# V1_illuminationBoard_sch.net
KiCad netlist of a schematic drawn in Altium Designer
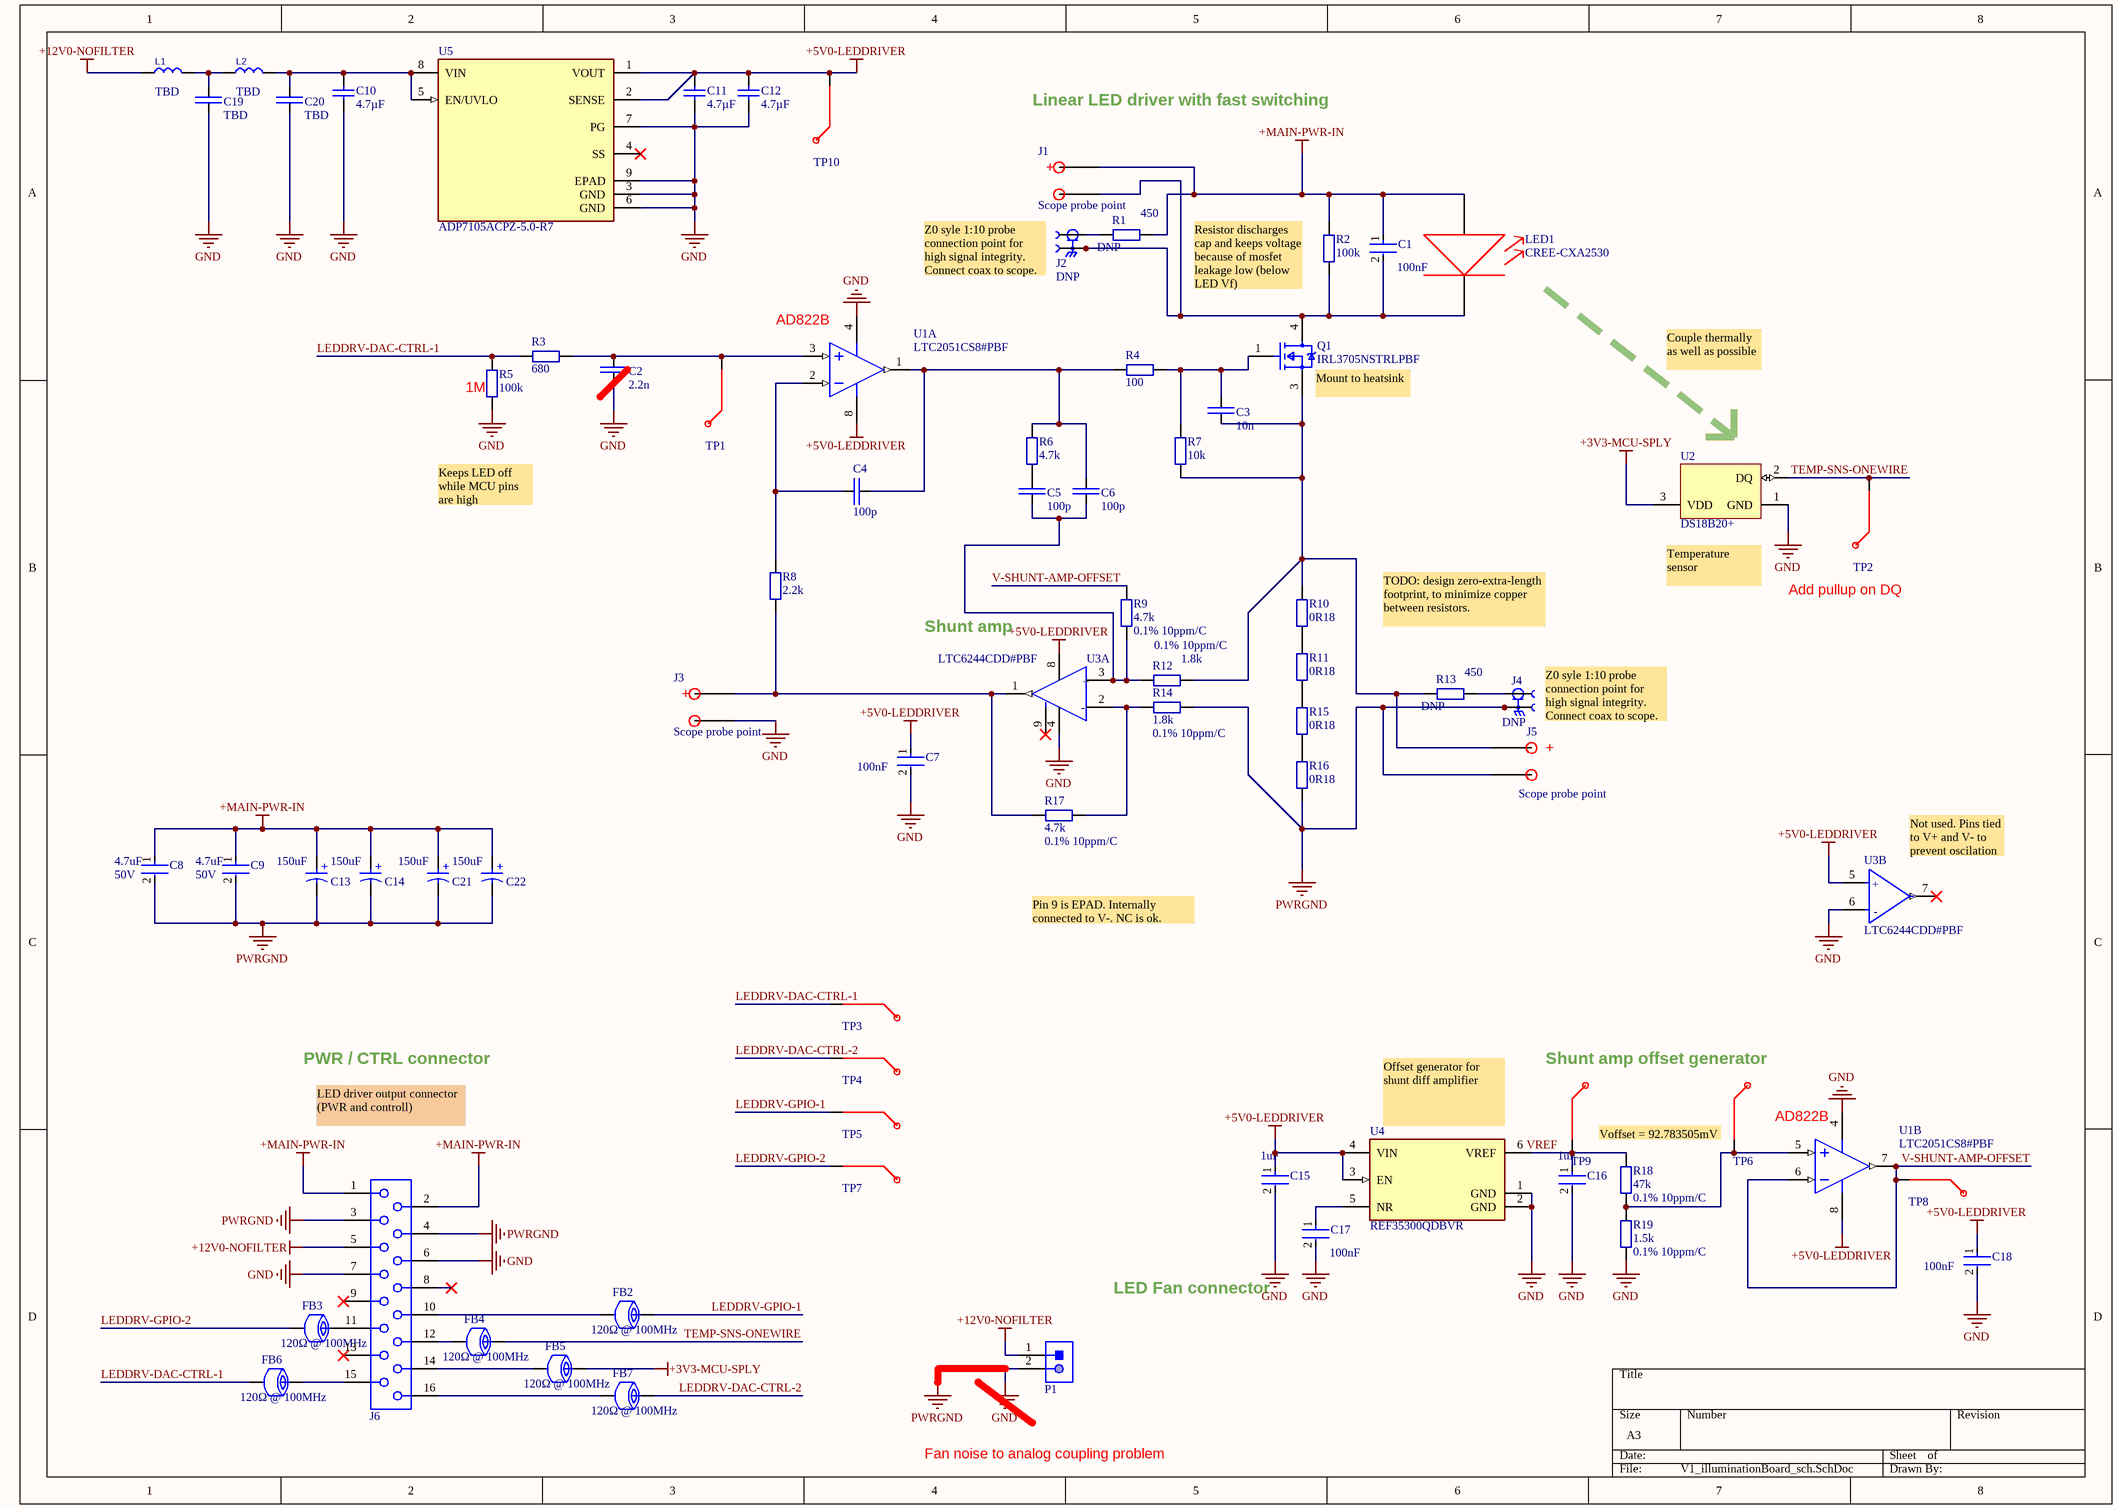
[diagram p0: V1_illuminationBoard_sch.SchDoc]

(export (version "E")
  (design (tool "Eeschema 10.0.6"))
  (components
    (comp (ref "C1")
      (value "885012206095")
      (footprint "FP-885012206095-IPC_B")
      (description "CAP CER 0.1UF 50V X7R 0603")
      (fields (field (name "TOLERANCE") "10%") (field (name "CAPACITANCE") "100nF"))
      (libsource (lib "Altium Content Vault") (part "11868f565c42a9108669ba33697ecf6"))
    )
    (comp (ref "C2")
      (value "2.2n")
      (footprint "Passives:FPR_0603_C_R0")
      (description "Capacitor - generic SMD")
      (fields (field (name "Comment") "PN_C0603_2n2"))
      (libsource (lib "Passives") (part "C"))
    )
    (comp (ref "C3")
      (value "10n")
      (footprint "Passives:FPR_0603_C_R0")
      (description "Capacitor - generic SMD")
      (fields (field (name "Comment") "PN_C0603_10n"))
      (libsource (lib "Passives") (part "C"))
    )
    (comp (ref "C4")
      (value "100p")
      (footprint "Passives:FPR_0603_C_R0")
      (description "Capacitor - generic SMD")
      (fields (field (name "Comment") "PN_C0603_100p"))
      (libsource (lib "Passives") (part "C"))
    )
    (comp (ref "C5")
      (value "100p")
      (footprint "Passives:FPR_0603_C_R0")
      (description "Capacitor - generic SMD")
      (fields (field (name "Comment") "PN_C0603_100p"))
      (libsource (lib "Passives") (part "C"))
    )
    (comp (ref "C6")
      (value "100p")
      (footprint "Passives:FPR_0603_C_R0")
      (description "Capacitor - generic SMD")
      (fields (field (name "Comment") "PN_C0603_100p"))
      (libsource (lib "Passives") (part "C"))
    )
    (comp (ref "C7")
      (value "885012206095")
      (footprint "FP-885012206095-IPC_B")
      (description "CAP CER 0.1UF 50V X7R 0603")
      (fields (field (name "TOLERANCE") "10%") (field (name "CAPACITANCE") "100nF"))
      (libsource (lib "Altium Content Vault") (part "11868f565c42a9108669ba33697ecf6"))
    )
    (comp (ref "C8")
      (value "885012208094")
      (footprint "FP-885012208094-IPC_B")
      (description "CAP CER 4.7UF 50V X7R 1206")
      (fields
        (field (name "VOLTAGE RATING (DC)") "50V")
        (field (name "CAPACITANCE") "4.7uF")
        (field (name "TOLERANCE") "10%")
      )
      (libsource (lib "Altium Content Vault") (part "11868f565c42a9108669ba33697ecf6"))
    )
    (comp (ref "C9")
      (value "885012208094")
      (footprint "FP-885012208094-IPC_B")
      (description "CAP CER 4.7UF 50V X7R 1206")
      (fields
        (field (name "VOLTAGE RATING (DC)") "50V")
        (field (name "CAPACITANCE") "4.7uF")
        (field (name "TOLERANCE") "10%")
      )
      (libsource (lib "Altium Content Vault") (part "11868f565c42a9108669ba33697ecf6"))
    )
    (comp (ref "C10")
      (value "885012107018")
      (footprint "WCAP-CSGP_0805_L2W1.25H1.25")
      (description "WCAP-CSGP Multilayer Ceramic Chip Capacitor, General Purpose, size 0805, X5R, 4.7µF, 25VDC")
      (fields (field (name "MANUFACTURER") "Wurth Elektronik") (field (name "CAPACITANCE") "4.7µF"))
      (libsource (lib "Altium_WCAP-CSGP (rev22f)") (part "885012107018"))
    )
    (comp (ref "C11")
      (value "885012107018")
      (footprint "WCAP-CSGP_0805_L2W1.25H1.25")
      (description "WCAP-CSGP Multilayer Ceramic Chip Capacitor, General Purpose, size 0805, X5R, 4.7µF, 25VDC")
      (fields (field (name "MANUFACTURER") "Wurth Elektronik") (field (name "CAPACITANCE") "4.7µF"))
      (libsource (lib "Altium_WCAP-CSGP (rev22f)") (part "885012107018"))
    )
    (comp (ref "C12")
      (value "885012107018")
      (footprint "WCAP-CSGP_0805_L2W1.25H1.25")
      (description "WCAP-CSGP Multilayer Ceramic Chip Capacitor, General Purpose, size 0805, X5R, 4.7µF, 25VDC")
      (fields (field (name "MANUFACTURER") "Wurth Elektronik") (field (name "CAPACITANCE") "4.7µF"))
      (libsource (lib "Altium_WCAP-CSGP (rev22f)") (part "885012107018"))
    )
    (comp (ref "C13")
      (value "865060657011")
      (footprint "WCAP-ASLL_D10H10.5")
      (description "WCAP-ASLL Aluminum Electrolytic Capacitor, V-Chip, D10 x H10.5mm, 150µF, 50V")
      (fields (field (name "MANUFACTURER") "Wurth Elektronik") (field (name "CAPACITANCE") "150uF"))
      (libsource (lib "Altium_WCAP-ASLL (rev22d)") (part "865060657011"))
    )
    (comp (ref "C14")
      (value "865060657011")
      (footprint "WCAP-ASLL_D10H10.5")
      (description "WCAP-ASLL Aluminum Electrolytic Capacitor, V-Chip, D10 x H10.5mm, 150µF, 50V")
      (fields (field (name "MANUFACTURER") "Wurth Elektronik") (field (name "CAPACITANCE") "150uF"))
      (libsource (lib "Altium_WCAP-ASLL (rev22d)") (part "865060657011"))
    )
    (comp (ref "C15")
      (value "885012207078")
      (footprint "FP-885012207078-IPC_B")
      (description "CAP CER 1UF 25V X7R 0805")
      (fields (field (name "CAPACITANCE") "1uF") (field (name "TOLERANCE") "10%"))
      (libsource (lib "Altium Content Vault") (part "b4654b650e69147ec39a6b967a45e02"))
    )
    (comp (ref "C16")
      (value "885012207078")
      (footprint "FP-885012207078-IPC_B")
      (description "CAP CER 1UF 25V X7R 0805")
      (fields (field (name "CAPACITANCE") "1uF") (field (name "TOLERANCE") "10%"))
      (libsource (lib "Altium Content Vault") (part "b4654b650e69147ec39a6b967a45e02"))
    )
    (comp (ref "C17")
      (value "885012206095")
      (footprint "FP-885012206095-IPC_B")
      (description "CAP CER 0.1UF 50V X7R 0603")
      (fields (field (name "TOLERANCE") "10%") (field (name "CAPACITANCE") "100nF"))
      (libsource (lib "Altium Content Vault") (part "11868f565c42a9108669ba33697ecf6"))
    )
    (comp (ref "C18")
      (value "885012206095")
      (footprint "FP-885012206095-IPC_B")
      (description "CAP CER 0.1UF 50V X7R 0603")
      (fields (field (name "TOLERANCE") "10%") (field (name "CAPACITANCE") "100nF"))
      (libsource (lib "Altium Content Vault") (part "11868f565c42a9108669ba33697ecf6"))
    )
    (comp (ref "C19")
      (value "TBD")
      (footprint "Passives:FPR_0603_C_R0")
      (description "Capacitor - generic SMD")
      (fields (field (name "Comment") "PN_C0603_TBD"))
      (libsource (lib "Passives") (part "C"))
    )
    (comp (ref "C20")
      (value "TBD")
      (footprint "Passives:FPR_0603_C_R0")
      (description "Capacitor - generic SMD")
      (fields (field (name "Comment") "PN_C0603_TBD"))
      (libsource (lib "Passives") (part "C"))
    )
    (comp (ref "C21")
      (value "865060657011")
      (footprint "WCAP-ASLL_D10H10.5")
      (description "WCAP-ASLL Aluminum Electrolytic Capacitor, V-Chip, D10 x H10.5mm, 150µF, 50V")
      (fields (field (name "MANUFACTURER") "Wurth Elektronik") (field (name "CAPACITANCE") "150uF"))
      (libsource (lib "Altium_WCAP-ASLL (rev22d)") (part "865060657011"))
    )
    (comp (ref "C22")
      (value "865060657011")
      (footprint "WCAP-ASLL_D10H10.5")
      (description "WCAP-ASLL Aluminum Electrolytic Capacitor, V-Chip, D10 x H10.5mm, 150µF, 50V")
      (fields (field (name "MANUFACTURER") "Wurth Elektronik") (field (name "CAPACITANCE") "150uF"))
      (libsource (lib "Altium_WCAP-ASLL (rev22d)") (part "865060657011"))
    )
    (comp (ref "FB2")
      (value "120Ω @ 100MHz")
      (footprint "SMD_0805")
      (description "Ferrite Bead, 0805 [2012 Metric], 120 ohm, 800 mA, BLM21A Series, 0.15 ohm, ± 25%")
      (fields (field (name "MANUFACTURER") "Murata"))
      (libsource (lib "DAQ_REV_B") (part "BLM21AG121SN1D"))
    )
    (comp (ref "FB3")
      (value "120Ω @ 100MHz")
      (footprint "SMD_0805")
      (description "Ferrite Bead, 0805 [2012 Metric], 120 ohm, 800 mA, BLM21A Series, 0.15 ohm, ± 25%")
      (fields (field (name "MANUFACTURER") "Murata"))
      (libsource (lib "DAQ_REV_B") (part "BLM21AG121SN1D"))
    )
    (comp (ref "FB4")
      (value "120Ω @ 100MHz")
      (footprint "SMD_0805")
      (description "Ferrite Bead, 0805 [2012 Metric], 120 ohm, 800 mA, BLM21A Series, 0.15 ohm, ± 25%")
      (fields (field (name "MANUFACTURER") "Murata"))
      (libsource (lib "DAQ_REV_B") (part "BLM21AG121SN1D"))
    )
    (comp (ref "FB5")
      (value "120Ω @ 100MHz")
      (footprint "SMD_0805")
      (description "Ferrite Bead, 0805 [2012 Metric], 120 ohm, 800 mA, BLM21A Series, 0.15 ohm, ± 25%")
      (fields (field (name "MANUFACTURER") "Murata"))
      (libsource (lib "DAQ_REV_B") (part "BLM21AG121SN1D"))
    )
    (comp (ref "FB6")
      (value "120Ω @ 100MHz")
      (footprint "SMD_0805")
      (description "Ferrite Bead, 0805 [2012 Metric], 120 ohm, 800 mA, BLM21A Series, 0.15 ohm, ± 25%")
      (fields (field (name "MANUFACTURER") "Murata"))
      (libsource (lib "DAQ_REV_B") (part "BLM21AG121SN1D"))
    )
    (comp (ref "FB7")
      (value "120Ω @ 100MHz")
      (footprint "SMD_0805")
      (description "Ferrite Bead, 0805 [2012 Metric], 120 ohm, 800 mA, BLM21A Series, 0.15 ohm, ± 25%")
      (fields (field (name "MANUFACTURER") "Murata"))
      (libsource (lib "DAQ_REV_B") (part "BLM21AG121SN1D"))
    )
    (comp (ref "J1")
      (value "Scope probe point")
      (footprint "scope with ground spring probe point")
      (libsource (lib "planinsekLib_sch") (part "Scope probe point"))
    )
    (comp (ref "J2")
      (value "CONUFL001-SMD-T")
      (footprint "LINX_CONUFL001-SMD-T")
      (description "U.FL (UMCC) Connector Jack, Male Pin 50Ohm Surface Mount Solder")
      (fields (field (name "MF") "Linx") (field (name "DNP") "DNP"))
      (libsource (lib "") (part "CONUFL001-SMD-T_1"))
    )
    (comp (ref "J3")
      (value "Scope probe point")
      (footprint "scope with ground spring probe point")
      (libsource (lib "planinsekLib_sch") (part "Scope probe point"))
    )
    (comp (ref "J4")
      (value "CONUFL001-SMD-T")
      (footprint "LINX_CONUFL001-SMD-T")
      (description "U.FL (UMCC) Connector Jack, Male Pin 50Ohm Surface Mount Solder")
      (fields (field (name "MF") "Linx") (field (name "DNP") "DNP"))
      (libsource (lib "CONUFL001-SMD-T") (part "CONUFL001-SMD-T"))
    )
    (comp (ref "J5")
      (value "Scope probe point")
      (footprint "scope with ground spring probe point")
      (libsource (lib "") (part "Scope probe point_1"))
    )
    (comp (ref "J6")
      (value "690368191672")
      (footprint "690368191672")
      (description "WR-MM Mini Module Connector, Female, THT, with Latch & Polarization, Angled, pitch 2.54mm, 16p")
      (fields (field (name "MANUFACTURER") "Wurth Elektronik"))
      (libsource (lib "Altium_WR-MM (rev22a)") (part "690368191672"))
    )
    (comp (ref "L1")
      (value "TBD")
      (footprint "FPR_1216_R_R0")
      (description "Inductor - generic SMD")
      (fields (field (name "Comment") "L-TBD"))
      (libsource (lib "Passives") (part "L"))
    )
    (comp (ref "L2")
      (value "TBD")
      (footprint "FPR_1216_R_R0")
      (description "Inductor - generic SMD")
      (fields (field (name "Comment") "L-TBD"))
      (libsource (lib "Passives") (part "L"))
    )
    (comp (ref "LED1")
      (value "CREE-CXA2530")
      (footprint "CXA2530-SolderMount")
      (description "High power LED")
      (libsource (lib "planinsekLib_sch") (part "CREE CXA2530"))
    )
    (comp (ref "P1")
      (value "61300211121")
      (footprint "61300211121")
      (description "THT Vertical Pin Header WR-PHD, Pitch 2.54 mm, Single Row, 2 pins")
      (fields (field (name "MANUFACTURER") "Wurth Elektronik") (field (name "PUBLISHER") "WurthElektronik"))
      (libsource (lib "Altium Content Vault") (part "WE-CN-1P-M-R2"))
    )
    (comp (ref "Q1")
      (value "IRL3705NSTRLPBF")
      (footprint "FP-PG-TO263-3-MFG")
      (description "MOSFET N-CH 55V 89A D2PAK")
      (libsource (lib "Altium Content Vault") (part "2f21c11e83d30f418bb422e5a3b3d11"))
    )
    (comp (ref "R1")
      (value "450")
      (footprint "Passives:FPR_0603_R_R0")
      (description "Resistor - generic SMD")
      (fields (field (name "DNP") "DNP") (field (name "Comment") "PN_R0603_450R"))
      (libsource (lib "Passives") (part "R"))
    )
    (comp (ref "R2")
      (value "100k")
      (footprint "Passives:FPR_0603_R_R0")
      (description "Resistor - generic SMD")
      (fields (field (name "Comment") "PN_R0603_100k"))
      (libsource (lib "Passives") (part "R"))
    )
    (comp (ref "R3")
      (value "680")
      (footprint "Passives:FPR_0603_R_R0")
      (description "Resistor - generic SMD")
      (fields (field (name "Comment") "PN_R0603_680R"))
      (libsource (lib "Passives") (part "R"))
    )
    (comp (ref "R4")
      (value "100")
      (footprint "Passives:FPR_0603_R_R0")
      (description "Resistor - generic SMD")
      (fields (field (name "Comment") "PN_R0603_100R"))
      (libsource (lib "Passives") (part "R"))
    )
    (comp (ref "R5")
      (value "100k")
      (footprint "Passives:FPR_0603_R_R0")
      (description "Resistor - generic SMD")
      (fields (field (name "Comment") "PN_R0603_100k"))
      (libsource (lib "Passives") (part "R"))
    )
    (comp (ref "R6")
      (value "4.7k")
      (footprint "Passives:FPR_0603_R_R0")
      (description "Resistor - generic SMD")
      (fields (field (name "Comment") "PN_R0603_4k7"))
      (libsource (lib "Passives") (part "R"))
    )
    (comp (ref "R7")
      (value "10k")
      (footprint "Passives:FPR_0603_R_R0")
      (description "Resistor - generic SMD")
      (fields (field (name "Comment") "PN_R0603_10k"))
      (libsource (lib "Passives") (part "R"))
    )
    (comp (ref "R8")
      (value "2.2k")
      (footprint "Passives:FPR_0603_R_R0")
      (description "Resistor - generic SMD")
      (fields (field (name "Comment") "PN_R0603_2k2"))
      (libsource (lib "Passives") (part "R"))
    )
    (comp (ref "R9")
      (value "4.7k")
      (footprint "Passives:FPR_0603_R_R0")
      (description "Resistor - generic SMD")
      (fields (field (name "TOLERANCE") "0.1% 10ppm/C") (field (name "Comment") "PN_R0603_4k7_0%1_10ppm"))
      (libsource (lib "Passives") (part "R"))
    )
    (comp (ref "R10")
      (value "0R18")
      (footprint "FPR_CRF2512_R0-endToEnd")
      (description "Resistor - generic SMD")
      (fields (field (name "Comment") "TLRP3A30CR180FTE"))
      (libsource (lib "Passives") (part "R"))
    )
    (comp (ref "R11")
      (value "0R18")
      (footprint "FPR_CRF2512_R0-endToEnd")
      (description "Resistor - generic SMD")
      (fields (field (name "Comment") "TLRP3A30CR180FTE"))
      (libsource (lib "Passives") (part "R"))
    )
    (comp (ref "R12")
      (value "1.8k")
      (footprint "Passives:FPR_0603_R_R0")
      (description "Resistor - generic SMD")
      (fields (field (name "TOLERANCE") "0.1% 10ppm/C") (field (name "Comment") "PN_R0603_1k8_0%1_10ppm"))
      (libsource (lib "Passives") (part "R"))
    )
    (comp (ref "R13")
      (value "450")
      (footprint "Passives:FPR_0603_R_R0")
      (description "Resistor - generic SMD")
      (fields (field (name "DNP") "DNP") (field (name "Comment") "PN_R0603_450R"))
      (libsource (lib "Passives") (part "R"))
    )
    (comp (ref "R14")
      (value "1.8k")
      (footprint "Passives:FPR_0603_R_R0")
      (description "Resistor - generic SMD")
      (fields (field (name "TOLERANCE") "0.1% 10ppm/C") (field (name "Comment") "PN_R0603_1k8_0%1_10ppm"))
      (libsource (lib "Passives") (part "R"))
    )
    (comp (ref "R15")
      (value "0R18")
      (footprint "FPR_CRF2512_R0-endToEnd")
      (description "Resistor - generic SMD")
      (fields (field (name "Comment") "TLRP3A30CR180FTE"))
      (libsource (lib "Passives") (part "R"))
    )
    (comp (ref "R16")
      (value "0R18")
      (footprint "FPR_CRF2512_R0-endToEnd")
      (description "Resistor - generic SMD")
      (fields (field (name "Comment") "TLRP3A30CR180FTE"))
      (libsource (lib "Passives") (part "R"))
    )
    (comp (ref "R17")
      (value "4.7k")
      (footprint "Passives:FPR_0603_R_R0")
      (description "Resistor - generic SMD")
      (fields (field (name "TOLERANCE") "0.1% 10ppm/C") (field (name "Comment") "PN_R0603_4k7_0%1_10ppm"))
      (libsource (lib "Passives") (part "R"))
    )
    (comp (ref "R18")
      (value "47k")
      (footprint "Passives:FPR_0603_R_R0")
      (description "Resistor - generic SMD")
      (fields (field (name "TOLERANCE") "0.1% 10ppm/C") (field (name "Comment") "PN_R0603_47k_0%1_10ppm"))
      (libsource (lib "Passives") (part "R"))
    )
    (comp (ref "R19")
      (value "1.5k")
      (footprint "Passives:FPR_0603_R_R0")
      (description "Resistor - generic SMD")
      (fields (field (name "TOLERANCE") "0.1% 10ppm/C") (field (name "Comment") "PN_R0603_1k5_0%1_10ppm"))
      (libsource (lib "Passives") (part "R"))
    )
    (comp (ref "TP1")
      (value "Test Point")
      (footprint "Test Point 1.5mm SMD")
      (libsource (lib "planinsekLib_sch") (part "Test Point"))
    )
    (comp (ref "TP2")
      (value "Test Point")
      (footprint "Test Point 1.5mm SMD")
      (libsource (lib "planinsekLib_sch") (part "Test Point"))
    )
    (comp (ref "TP3")
      (value "Test Point")
      (footprint "Test Point 1.5mm SMD")
      (libsource (lib "planinsekLib_sch") (part "Test Point"))
    )
    (comp (ref "TP4")
      (value "Test Point")
      (footprint "Test Point 1.5mm SMD")
      (libsource (lib "planinsekLib_sch") (part "Test Point"))
    )
    (comp (ref "TP5")
      (value "Test Point")
      (footprint "Test Point 1.5mm SMD")
      (libsource (lib "planinsekLib_sch") (part "Test Point"))
    )
    (comp (ref "TP6")
      (value "Test Point")
      (footprint "Test Point 1.5mm SMD")
      (libsource (lib "planinsekLib_sch") (part "Test Point"))
    )
    (comp (ref "TP7")
      (value "Test Point")
      (footprint "Test Point 1.5mm SMD")
      (libsource (lib "planinsekLib_sch") (part "Test Point"))
    )
    (comp (ref "TP8")
      (value "Test Point")
      (footprint "Test Point 1.5mm SMD")
      (libsource (lib "planinsekLib_sch") (part "Test Point"))
    )
    (comp (ref "TP9")
      (value "Test Point")
      (footprint "Test Point 1.5mm SMD")
      (libsource (lib "planinsekLib_sch") (part "Test Point"))
    )
    (comp (ref "TP10")
      (value "Test Point")
      (footprint "Test Point 1.5mm SMD")
      (libsource (lib "planinsekLib_sch") (part "Test Point"))
    )
    (comp (ref "U1")
      (value "LTC2051CS8#PBF")
      (footprint "LT-S8-8_N")
      (fields
        (field (name "MANUFACTURER") "Linear Technology")
        (field (name "LINEAR TECHNOLOGY PART NUMBER") "LTC2051")
      )
      (libsource (lib "Altium Content Vault") (part "LT-LT1364-LT18XX-8"))
    )
    (comp (ref "U2")
      (value "DS18B20+")
      (footprint "to-92 horiyontal boardhole")
      (libsource (lib "ds18b20") (part "CMP-0253-00003-1"))
    )
    (comp (ref "U3")
      (value "LTC6244CDD#PBF")
      (footprint "FP-DD-8-05-08-1698-IPC_A")
      (description "IC CMOS 2 CIRCUIT 8DFN")
      (libsource (lib "Altium Content Vault") (part "2f377bccdb376714fb973d3e24d9851"))
    )
    (comp (ref "U4")
      (value "REF35300QDBVR")
      (footprint "FP-DBV0006A-MFG")
      (description "650-NA QUIESCENT CURRENT, 12-PPM, 3V out")
      (libsource (lib "Altium Content Vault") (part "73067d3f248247d8aed0d86424b3493"))
    )
    (comp (ref "U5")
      (value "ADP7105ACPZ-5.0-R7")
      (footprint "FP-CP-8-5-IPC_C")
      (description "IC REG LINEAR 5V 500MA 8LFCSP")
      (libsource (lib "Altium Content Vault") (part "3afc8f7b7a475b796d1e7b3a9bf20b9"))
    )
  )
  (nets
    (net (code "1") (name "+3V3-MCU-SPLY") (class "Default")
      (node (ref "FB5") (pin "1") (pintype "passive"))
      (node (ref "U2") (pin "3") (pinfunction "VDD_3") (pintype "power_in"))
    )
    (net (code "2") (name "+5V0-LEDDRIVER") (class "Default")
      (node (ref "C11") (pin "2") (pinfunction "2_2") (pintype "passive"))
      (node (ref "C12") (pin "2") (pinfunction "2_2") (pintype "passive"))
      (node (ref "C15") (pin "1") (pinfunction "1_1") (pintype "passive"))
      (node (ref "C18") (pin "1") (pinfunction "1_1") (pintype "passive"))
      (node (ref "C7") (pin "1") (pinfunction "1_1") (pintype "passive"))
      (node (ref "TP10") (pin "1") (pintype "passive"))
      (node (ref "U1") (pin "8") (pinfunction "V+_8") (pintype "power_in"))
      (node (ref "U3") (pin "5") (pinfunction "+IN_B_5") (pintype "tri_state"))
      (node (ref "U3") (pin "8") (pinfunction "V+_8") (pintype "power_in"))
      (node (ref "U4") (pin "3") (pinfunction "EN_3") (pintype "input"))
      (node (ref "U4") (pin "4") (pinfunction "VIN_4") (pintype "power_in"))
      (node (ref "U5") (pin "1") (pinfunction "VOUT_1") (pintype "power_in"))
      (node (ref "U5") (pin "2") (pinfunction "SENSE_2") (pintype "power_in"))
    )
    (net (code "3") (name "+12V0-NOFILTER") (class "Default")
      (node (ref "J6") (pin "5") (pinfunction "5_5") (pintype "passive"))
      (node (ref "L1") (pin "1") (pintype "passive"))
      (node (ref "P1") (pin "1") (pinfunction "1_1") (pintype "passive"))
    )
    (net (code "4") (name "+MAIN-PWR-IN") (class "Default")
      (node (ref "C1") (pin "1") (pinfunction "1_1") (pintype "passive"))
      (node (ref "C13") (pin "1") (pinfunction "P_1") (pintype "passive"))
      (node (ref "C14") (pin "1") (pinfunction "P_1") (pintype "passive"))
      (node (ref "C21") (pin "1") (pinfunction "P_1") (pintype "passive"))
      (node (ref "C22") (pin "1") (pinfunction "P_1") (pintype "passive"))
      (node (ref "C8") (pin "1") (pinfunction "1_1") (pintype "passive"))
      (node (ref "C9") (pin "1") (pinfunction "1_1") (pintype "passive"))
      (node (ref "J1") (pin "POS") (pinfunction "POS_POS") (pintype "passive"))
      (node (ref "J6") (pin "1") (pinfunction "1_1") (pintype "passive"))
      (node (ref "J6") (pin "2") (pinfunction "2_2") (pintype "passive"))
      (node (ref "LED1") (pin "POS") (pinfunction "POS_POS") (pintype "passive"))
      (node (ref "R1") (pin "2") (pinfunction "2_2") (pintype "passive"))
      (node (ref "R2") (pin "2") (pinfunction "2_2") (pintype "passive"))
    )
    (net (code "5") (name "/LEDDRV-DAC-CTRL-1") (class "Default")
      (node (ref "FB6") (pin "2") (pintype "passive"))
      (node (ref "R3") (pin "2") (pinfunction "2_2") (pintype "passive"))
      (node (ref "R5") (pin "2") (pinfunction "2_2") (pintype "passive"))
      (node (ref "TP3") (pin "1") (pintype "passive"))
    )
    (net (code "6") (name "/LEDDRV-DAC-CTRL-2") (class "Default")
      (node (ref "FB7") (pin "1") (pintype "passive"))
      (node (ref "TP4") (pin "1") (pintype "passive"))
    )
    (net (code "7") (name "/LEDDRV-GPIO-1") (class "Default")
      (node (ref "FB2") (pin "1") (pintype "passive"))
      (node (ref "TP5") (pin "1") (pintype "passive"))
    )
    (net (code "8") (name "/LEDDRV-GPIO-2") (class "Default")
      (node (ref "FB3") (pin "2") (pintype "passive"))
      (node (ref "TP7") (pin "1") (pintype "passive"))
    )
    (net (code "9") (name "/TEMP-SNS-ONEWIRE") (class "Default")
      (node (ref "FB4") (pin "1") (pintype "passive"))
      (node (ref "TP2") (pin "1") (pintype "passive"))
      (node (ref "U2") (pin "2") (pinfunction "DQ_2") (pintype "bidirectional"))
    )
    (net (code "10") (name "/V-SHUNT-AMP-OFFSET") (class "Default")
      (node (ref "R9") (pin "2") (pinfunction "2_2") (pintype "passive"))
      (node (ref "TP8") (pin "1") (pintype "passive"))
      (node (ref "U1") (pin "6") (pinfunction "-IN_B_6") (pintype "input"))
      (node (ref "U1") (pin "7") (pinfunction "OUT_B_7") (pintype "output"))
    )
    (net (code "11") (name "/VREF") (class "Default")
      (node (ref "C16") (pin "1") (pinfunction "1_1") (pintype "passive"))
      (node (ref "R18") (pin "1") (pinfunction "1_1") (pintype "passive"))
      (node (ref "TP9") (pin "1") (pintype "passive"))
      (node (ref "U4") (pin "6") (pinfunction "VREF_6") (pintype "passive"))
    )
    (net (code "12") (name "GND") (class "Default")
      (node (ref "C10") (pin "1") (pinfunction "1_1") (pintype "passive"))
      (node (ref "C11") (pin "1") (pinfunction "1_1") (pintype "passive"))
      (node (ref "C12") (pin "1") (pinfunction "1_1") (pintype "passive"))
      (node (ref "C15") (pin "2") (pinfunction "2_2") (pintype "passive"))
      (node (ref "C16") (pin "2") (pinfunction "2_2") (pintype "passive"))
      (node (ref "C17") (pin "2") (pinfunction "2_2") (pintype "passive"))
      (node (ref "C18") (pin "2") (pinfunction "2_2") (pintype "passive"))
      (node (ref "C19") (pin "1") (pinfunction "1_1") (pintype "passive"))
      (node (ref "C2") (pin "2") (pinfunction "2_2") (pintype "passive"))
      (node (ref "C20") (pin "1") (pinfunction "1_1") (pintype "passive"))
      (node (ref "C7") (pin "2") (pinfunction "2_2") (pintype "passive"))
      (node (ref "J3") (pin "NEG") (pinfunction "NEG_NEG") (pintype "passive"))
      (node (ref "J6") (pin "6") (pinfunction "6_6") (pintype "passive"))
      (node (ref "J6") (pin "7") (pinfunction "7_7") (pintype "passive"))
      (node (ref "P1") (pin "2") (pinfunction "2_2") (pintype "passive"))
      (node (ref "R19") (pin "2") (pinfunction "2_2") (pintype "passive"))
      (node (ref "R5") (pin "1") (pinfunction "1_1") (pintype "passive"))
      (node (ref "U1") (pin "4") (pinfunction "V-_4") (pintype "power_in"))
      (node (ref "U2") (pin "1") (pinfunction "GND_1") (pintype "power_in"))
      (node (ref "U3") (pin "4") (pinfunction "V-_4") (pintype "power_in"))
      (node (ref "U3") (pin "6") (pinfunction "-IN_B_6") (pintype "tri_state"))
      (node (ref "U4") (pin "1") (pinfunction "GND_1") (pintype "power_in"))
      (node (ref "U4") (pin "2") (pinfunction "GND_2") (pintype "power_in"))
      (node (ref "U5") (pin "3") (pinfunction "GND_3") (pintype "power_in"))
      (node (ref "U5") (pin "6") (pinfunction "GND_6") (pintype "power_in"))
      (node (ref "U5") (pin "7") (pinfunction "PG_7") (pintype "open_collector"))
      (node (ref "U5") (pin "9") (pinfunction "EPAD_9") (pintype "power_in"))
    )
    (net (code "13") (name "Net-(C5-Pad1)") (class "Default")
      (node (ref "C5") (pin "1") (pinfunction "1_1") (pintype "passive"))
      (node (ref "R6") (pin "1") (pinfunction "1_1") (pintype "passive"))
    )
    (net (code "14") (name "Net-(C19-Pad2)") (class "Default")
      (node (ref "C19") (pin "2") (pinfunction "2_2") (pintype "passive"))
      (node (ref "L1") (pin "2") (pintype "passive"))
      (node (ref "L2") (pin "1") (pintype "passive"))
    )
    (net (code "15") (name "Net-(FB2-Pad2)") (class "Default")
      (node (ref "FB2") (pin "2") (pintype "passive"))
      (node (ref "J6") (pin "10") (pinfunction "10_10") (pintype "passive"))
    )
    (net (code "16") (name "Net-(FB3-Pad1)") (class "Default")
      (node (ref "FB3") (pin "1") (pintype "passive"))
      (node (ref "J6") (pin "11") (pinfunction "11_11") (pintype "passive"))
    )
    (net (code "17") (name "Net-(FB4-Pad2)") (class "Default")
      (node (ref "FB4") (pin "2") (pintype "passive"))
      (node (ref "J6") (pin "12") (pinfunction "12_12") (pintype "passive"))
    )
    (net (code "18") (name "Net-(FB5-Pad2)") (class "Default")
      (node (ref "FB5") (pin "2") (pintype "passive"))
      (node (ref "J6") (pin "14") (pinfunction "14_14") (pintype "passive"))
    )
    (net (code "19") (name "Net-(FB6-Pad1)") (class "Default")
      (node (ref "FB6") (pin "1") (pintype "passive"))
      (node (ref "J6") (pin "15") (pinfunction "15_15") (pintype "passive"))
    )
    (net (code "20") (name "Net-(FB7-Pad2)") (class "Default")
      (node (ref "FB7") (pin "2") (pintype "passive"))
      (node (ref "J6") (pin "16") (pinfunction "16_16") (pintype "passive"))
    )
    (net (code "21") (name "Net-(J2-Pad1)") (class "Default")
      (node (ref "J2") (pin "1") (pinfunction "1_1") (pintype "passive"))
      (node (ref "R1") (pin "1") (pinfunction "1_1") (pintype "passive"))
    )
    (net (code "22") (name "Net-(J4-Pad1)") (class "Default")
      (node (ref "J4") (pin "1") (pinfunction "1_1") (pintype "passive"))
      (node (ref "R13") (pin "1") (pinfunction "1_1") (pintype "passive"))
    )
    (net (code "23") (name "Net-(Q1-DRAIN)") (class "Default")
      (node (ref "C1") (pin "2") (pinfunction "2_2") (pintype "passive"))
      (node (ref "J1") (pin "NEG") (pinfunction "NEG_NEG") (pintype "passive"))
      (node (ref "J2") (pin "2") (pinfunction "2_2") (pintype "passive"))
      (node (ref "J2") (pin "3") (pinfunction "2_3") (pintype "passive"))
      (node (ref "LED1") (pin "NEG") (pinfunction "NEG_NEG") (pintype "passive"))
      (node (ref "Q1") (pin "4") (pinfunction "DRAIN_4") (pintype "passive"))
      (node (ref "R2") (pin "1") (pinfunction "1_1") (pintype "passive"))
    )
    (net (code "24") (name "Net-(Q1-GATE)") (class "Default")
      (node (ref "C3") (pin "2") (pinfunction "2_2") (pintype "passive"))
      (node (ref "Q1") (pin "1") (pinfunction "GATE_1") (pintype "passive"))
      (node (ref "R4") (pin "2") (pinfunction "2_2") (pintype "passive"))
      (node (ref "R7") (pin "2") (pinfunction "2_2") (pintype "passive"))
    )
    (net (code "25") (name "Net-(Q1-SOURCE)") (class "Default")
      (node (ref "C3") (pin "1") (pinfunction "1_1") (pintype "passive"))
      (node (ref "J5") (pin "POS") (pinfunction "POS_POS") (pintype "passive"))
      (node (ref "Q1") (pin "3") (pinfunction "SOURCE_3") (pintype "passive"))
      (node (ref "R10") (pin "2") (pinfunction "2_2") (pintype "passive"))
      (node (ref "R12") (pin "1") (pinfunction "1_1") (pintype "passive"))
      (node (ref "R13") (pin "2") (pinfunction "2_2") (pintype "passive"))
      (node (ref "R7") (pin "1") (pinfunction "1_1") (pintype "passive"))
    )
    (net (code "26") (name "Net-(R10-Pad1)") (class "Default")
      (node (ref "R10") (pin "1") (pinfunction "1_1") (pintype "passive"))
      (node (ref "R11") (pin "2") (pinfunction "2_2") (pintype "passive"))
    )
    (net (code "27") (name "Net-(R11-Pad1)") (class "Default")
      (node (ref "R11") (pin "1") (pinfunction "1_1") (pintype "passive"))
      (node (ref "R15") (pin "2") (pinfunction "2_2") (pintype "passive"))
    )
    (net (code "28") (name "Net-(R15-Pad1)") (class "Default")
      (node (ref "R15") (pin "1") (pinfunction "1_1") (pintype "passive"))
      (node (ref "R16") (pin "2") (pinfunction "2_2") (pintype "passive"))
    )
    (net (code "29") (name "Net-(U1A-+IN_A)") (class "Default")
      (node (ref "C2") (pin "1") (pinfunction "1_1") (pintype "passive"))
      (node (ref "R3") (pin "1") (pinfunction "1_1") (pintype "passive"))
      (node (ref "TP1") (pin "1") (pintype "passive"))
      (node (ref "U1") (pin "3") (pinfunction "+IN_A_3") (pintype "input"))
    )
    (net (code "30") (name "Net-(U1A--IN_A)") (class "Default")
      (node (ref "C4") (pin "2") (pinfunction "2_2") (pintype "passive"))
      (node (ref "R8") (pin "2") (pinfunction "2_2") (pintype "passive"))
      (node (ref "U1") (pin "2") (pinfunction "-IN_A_2") (pintype "input"))
    )
    (net (code "31") (name "Net-(U1A-OUT_A)") (class "Default")
      (node (ref "C4") (pin "1") (pinfunction "1_1") (pintype "passive"))
      (node (ref "C6") (pin "1") (pinfunction "1_1") (pintype "passive"))
      (node (ref "R4") (pin "1") (pinfunction "1_1") (pintype "passive"))
      (node (ref "R6") (pin "2") (pinfunction "2_2") (pintype "passive"))
      (node (ref "U1") (pin "1") (pinfunction "OUT_A_1") (pintype "output"))
    )
    (net (code "32") (name "Net-(U1B-+IN_B)") (class "Default")
      (node (ref "R18") (pin "2") (pinfunction "2_2") (pintype "passive"))
      (node (ref "R19") (pin "1") (pinfunction "1_1") (pintype "passive"))
      (node (ref "TP6") (pin "1") (pintype "passive"))
      (node (ref "U1") (pin "5") (pinfunction "+IN_B_5") (pintype "input"))
    )
    (net (code "33") (name "Net-(U3A-+IN_A)") (class "Default")
      (node (ref "C5") (pin "2") (pinfunction "2_2") (pintype "passive"))
      (node (ref "C6") (pin "2") (pinfunction "2_2") (pintype "passive"))
      (node (ref "R12") (pin "2") (pinfunction "2_2") (pintype "passive"))
      (node (ref "R9") (pin "1") (pinfunction "1_1") (pintype "passive"))
      (node (ref "U3") (pin "3") (pinfunction "+IN_A_3") (pintype "tri_state"))
    )
    (net (code "34") (name "Net-(U3A--IN_A)") (class "Default")
      (node (ref "R14") (pin "1") (pinfunction "1_1") (pintype "passive"))
      (node (ref "R17") (pin "2") (pinfunction "2_2") (pintype "passive"))
      (node (ref "U3") (pin "2") (pinfunction "-IN_A_2") (pintype "tri_state"))
    )
    (net (code "35") (name "Net-(U3A-OUT_A)") (class "Default")
      (node (ref "J3") (pin "POS") (pinfunction "POS_POS") (pintype "passive"))
      (node (ref "R17") (pin "1") (pinfunction "1_1") (pintype "passive"))
      (node (ref "R8") (pin "1") (pinfunction "1_1") (pintype "passive"))
      (node (ref "U3") (pin "1") (pinfunction "OUT_A_1") (pintype "output"))
    )
    (net (code "36") (name "Net-(U4-NR)") (class "Default")
      (node (ref "C17") (pin "1") (pinfunction "1_1") (pintype "passive"))
      (node (ref "U4") (pin "5") (pinfunction "NR_5") (pintype "passive"))
    )
    (net (code "37") (name "Net-(U5-EN{slash}UVLO)") (class "Default")
      (node (ref "C10") (pin "2") (pinfunction "2_2") (pintype "passive"))
      (node (ref "C20") (pin "2") (pinfunction "2_2") (pintype "passive"))
      (node (ref "L2") (pin "2") (pintype "passive"))
      (node (ref "U5") (pin "5") (pinfunction "EN/UVLO_5") (pintype "input"))
      (node (ref "U5") (pin "8") (pinfunction "VIN_8") (pintype "power_in"))
    )
    (net (code "38") (name "PWRGND") (class "Default")
      (node (ref "C13") (pin "2") (pinfunction "N_2") (pintype "passive"))
      (node (ref "C14") (pin "2") (pinfunction "N_2") (pintype "passive"))
      (node (ref "C21") (pin "2") (pinfunction "N_2") (pintype "passive"))
      (node (ref "C22") (pin "2") (pinfunction "N_2") (pintype "passive"))
      (node (ref "C8") (pin "2") (pinfunction "2_2") (pintype "passive"))
      (node (ref "C9") (pin "2") (pinfunction "2_2") (pintype "passive"))
      (node (ref "J4") (pin "2") (pinfunction "2_2") (pintype "passive"))
      (node (ref "J4") (pin "3") (pinfunction "2_3") (pintype "passive"))
      (node (ref "J5") (pin "NEG") (pinfunction "NEG_NEG") (pintype "passive"))
      (node (ref "J6") (pin "3") (pinfunction "3_3") (pintype "passive"))
      (node (ref "J6") (pin "4") (pinfunction "4_4") (pintype "passive"))
      (node (ref "R14") (pin "2") (pinfunction "2_2") (pintype "passive"))
      (node (ref "R16") (pin "1") (pinfunction "1_1") (pintype "passive"))
    )
    (net (code "39") (name "unconnected-(J6-Pad8)") (class "Default")
      (node (ref "J6") (pin "8") (pinfunction "8_8") (pintype "passive+no_connect"))
    )
    (net (code "40") (name "unconnected-(J6-Pad9)") (class "Default")
      (node (ref "J6") (pin "9") (pinfunction "9_9") (pintype "passive+no_connect"))
    )
    (net (code "41") (name "unconnected-(J6-Pad13)") (class "Default")
      (node (ref "J6") (pin "13") (pinfunction "13_13") (pintype "passive+no_connect"))
    )
    (net (code "42") (name "unconnected-(U3A-V--Pad9)") (class "Default")
      (node (ref "U3") (pin "9") (pinfunction "V-_9") (pintype "power_in+no_connect"))
    )
    (net (code "43") (name "unconnected-(U3B-OUT_B-Pad7)") (class "Default")
      (node (ref "U3") (pin "7") (pinfunction "OUT_B_7") (pintype "output+no_connect"))
    )
    (net (code "44") (name "unconnected-(U5-SS-Pad4)") (class "Default")
      (node (ref "U5") (pin "4") (pinfunction "SS_4") (pintype "passive+no_connect"))
    )
  )
)
